# power.net
KiCad netlist of a schematic drawn in Altium Designer
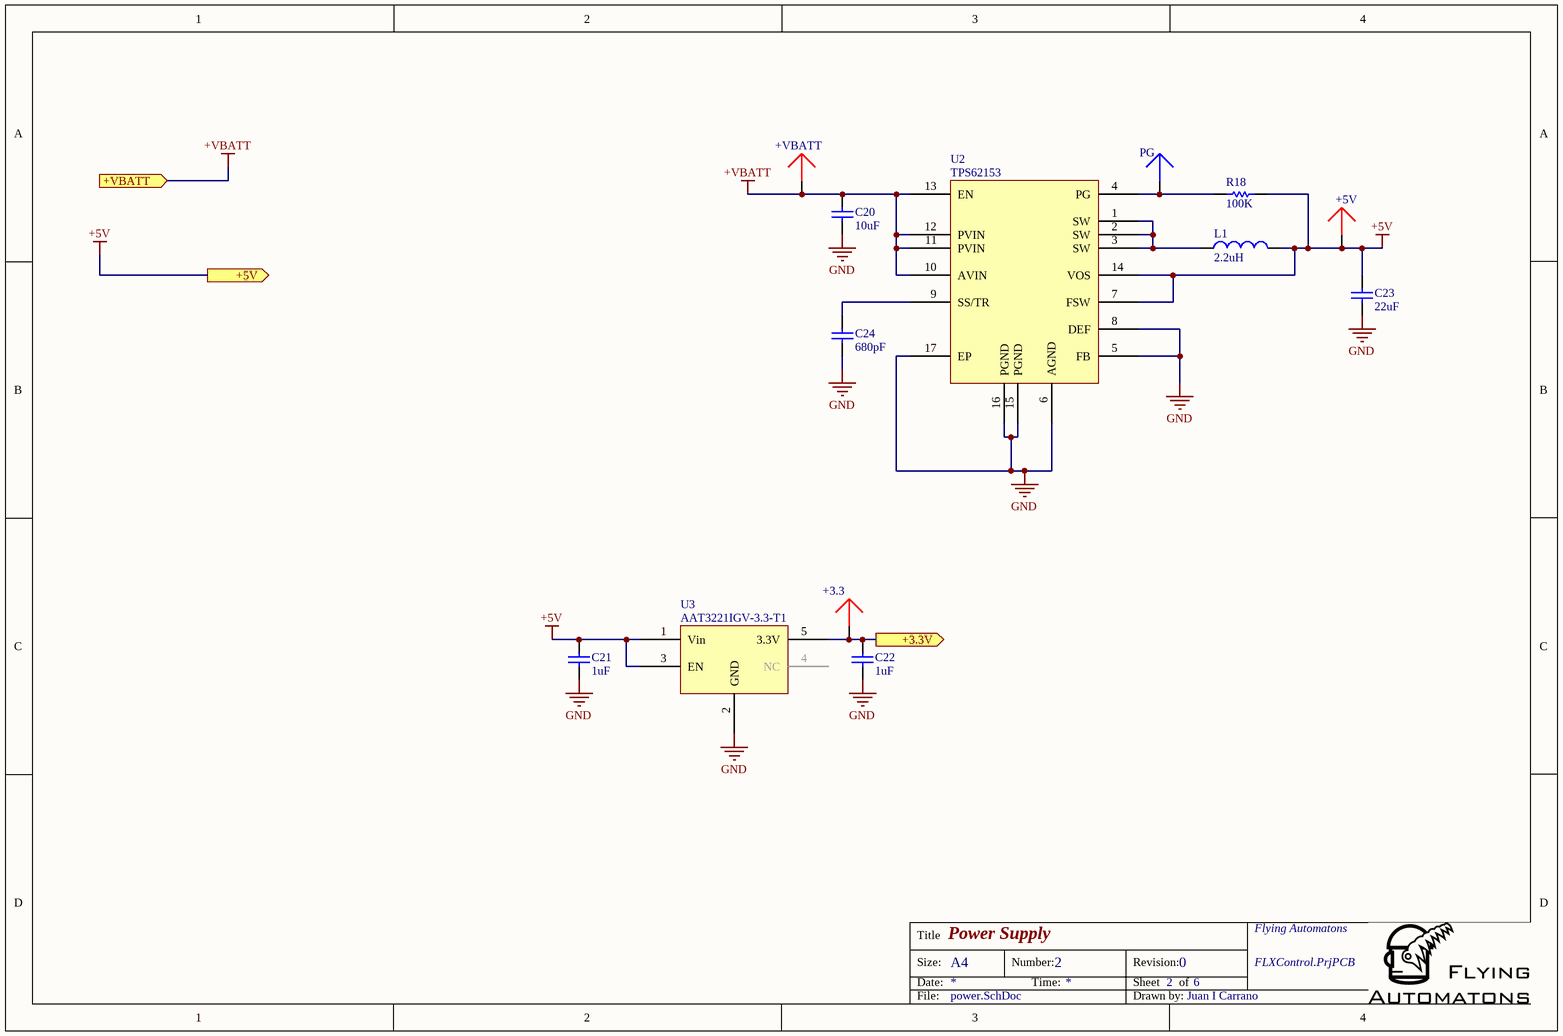
[diagram p0: power.SchDoc]

(export (version "E")
  (design (tool "Eeschema 10.0.6"))
  (components
    (comp (ref "+3.3")
      (value "TESTPOINT-ARROW-RED")
      (footprint "G-PIN_1mm-CIRCLE")
      (description "Tespoint for Power Trace")
      (libsource (lib "Connector#csv") (part "TESTP_PWR_1mm"))
    )
    (comp (ref "+5V")
      (value "TESTPOINT-ARROW-RED")
      (footprint "G-PIN_1mm-CIRCLE")
      (description "Tespoint for Power Trace")
      (libsource (lib "Connector#csv") (part "TESTP_PWR_1mm"))
    )
    (comp (ref "+VBATT")
      (value "TESTPOINT-ARROW-RED")
      (footprint "G-PIN_1mm-CIRCLE")
      (description "Tespoint for Power Trace")
      (libsource (lib "Connector#csv") (part "TESTP_PWR_1mm"))
    )
    (comp (ref "C20")
      (value "10uF")
      (footprint "CAPC3216L")
      (description "CAP CER 10UF 25V Y5V 1206")
      (fields (field (name "MANUFACTURER PART NUMBER") "TMK316F106ZL-T"))
      (libsource (lib "Passive#csv") (part "CAP_10u_1206_25V_Y5V"))
    )
    (comp (ref "C21")
      (value "1uF")
      (footprint "CAPC1608L")
      (description "CAP CER 1UF 25V 10% X5R 0603")
      (fields (field (name "MANUFACTURER PART NUMBER") "TMK107BJ105KA-T"))
      (libsource (lib "Passive#csv") (part "CAP_1u_0603_25V_X5R_10%"))
    )
    (comp (ref "C22")
      (value "1uF")
      (footprint "CAPC1608L")
      (description "CAP CER 1UF 25V 10% X5R 0603")
      (fields (field (name "MANUFACTURER PART NUMBER") "TMK107BJ105KA-T"))
      (libsource (lib "Passive#csv") (part "CAP_1u_0603_25V_X5R_10%"))
    )
    (comp (ref "C23")
      (value "22uF")
      (footprint "CAPC3216L")
      (description "CAP CER 22UF 16V 10% X5R 1206")
      (fields
        (field (name "MANUFACTURER") "Samsung Electro-Mechanics America, Inc")
        (field (name "MANUFACTURER PART NUMBER") "CL31A226KOCLFNC")
      )
      (libsource (lib "Passive#csv") (part "CAP_22u_1206_16V_X5R_10%"))
    )
    (comp (ref "C24")
      (value "680pF")
      (footprint "CAPC1608L")
      (description "CAP CER 680PF 50V 5% NP0 0603")
      (fields
        (field (name "MANUFACTURER") "Samsung Electro-Mechanics America, Inc")
        (field (name "MANUFACTURER PART NUMBER") "CL10C681JB8NFNC")
      )
      (libsource (lib "Passive#csv") (part "CAP_680p_0603_50V_NP0_5%"))
    )
    (comp (ref "L1")
      (value "2.2uH")
      (footprint "X-TDK_FLF3215")
      (description "INDUCTOR 2.2UH 1.4A 20% SMD")
      (fields
        (field (name "MANUFACTURER") "TDK Corporation")
        (field (name "MANUFACTURER PART NUMBER") "FLF3215T-2R2M")
      )
      (libsource (lib "Passive#csv") (part "IND_2u2_SMD_1A4_20%_3.2x2.5"))
    )
    (comp (ref "PG")
      (value "TESTPOINT-ARROW-BLUE")
      (footprint "G-PIN_1mm-CIRCLE")
      (description "Tespoint")
      (libsource (lib "Connector#csv") (part "TESTP_SIG_1mm"))
    )
    (comp (ref "R18")
      (value "100K")
      (footprint "RESC1608L")
      (description "RES 100K OHM 1/10W 1% 0603 SMD")
      (fields
        (field (name "MANUFACTURER") "Rohm Semiconductor")
        (field (name "MANUFACTURER PART NUMBER") "MCR03ERTF1003")
      )
      (libsource (lib "Passive#csv") (part "RES_100K_0603_0W1_1%"))
    )
    (comp (ref "U2")
      (value "TPS6215x")
      (footprint "JEDEC_MO-220VEED-4")
      (description "3-17V 1A Step-Down Converter in 3x3 QFN Package")
      (fields
        (field (name "MANUFACTURER PART NUMBER") "TPS62153")
        (field (name "MANUFACTURER") "Texas Instruments")
        (field (name "DRAWN BY") "Juan I Carrano")
      )
      (libsource (lib "Power_IC#csv") (part "x-TI_TPS62153"))
    )
    (comp (ref "U3")
      (value "LREG_3T_5pinA_EN_3.3V")
      (footprint "JEDEC_MO-178AA")
      (description "150 mA LDO Linear Regulator, SOT23-5")
      (fields
        (field (name "MANUFACTURER") "Skyworks Solutions Inc")
        (field (name "MANUFACTURER PART NUMBER") "AAT3221IGV-3.3-T1")
      )
      (libsource (lib "Power_IC#csv") (part "g-LREG_3V3_0A15_EN_SOT753"))
    )
  )
  (nets
    (net (code "1") (name "+5V") (class "Default")
      (node (ref "+5V") (pin "1") (pinfunction "1_1") (pintype "passive"))
      (node (ref "C21") (pin "1") (pinfunction "1_1") (pintype "passive"))
      (node (ref "C23") (pin "1") (pinfunction "1_1") (pintype "passive"))
      (node (ref "L1") (pin "2") (pinfunction "2_2") (pintype "passive"))
      (node (ref "R18") (pin "1") (pinfunction "1_1") (pintype "passive"))
      (node (ref "U2") (pin "14") (pinfunction "VOS_14") (pintype "passive"))
      (node (ref "U2") (pin "7") (pinfunction "FSW_7") (pintype "passive"))
      (node (ref "U3") (pin "1") (pinfunction "Vin_1") (pintype "power_in"))
      (node (ref "U3") (pin "3") (pinfunction "EN_3") (pintype "passive"))
    )
    (net (code "2") (name "+VBATT") (class "Default")
      (node (ref "+VBATT") (pin "1") (pinfunction "1_1") (pintype "passive"))
      (node (ref "C20") (pin "1") (pinfunction "1_1") (pintype "passive"))
      (node (ref "U2") (pin "10") (pinfunction "AVIN_10") (pintype "passive"))
      (node (ref "U2") (pin "11") (pinfunction "PVIN_11") (pintype "passive"))
      (node (ref "U2") (pin "12") (pinfunction "PVIN_12") (pintype "passive"))
      (node (ref "U2") (pin "13") (pinfunction "EN_13") (pintype "passive"))
    )
    (net (code "3") (name "/+3.3V") (class "Default")
      (node (ref "+3.3") (pin "1") (pinfunction "1_1") (pintype "passive"))
      (node (ref "C22") (pin "1") (pinfunction "1_1") (pintype "passive"))
      (node (ref "U3") (pin "5") (pinfunction "3.3V_5") (pintype "power_in"))
    )
    (net (code "4") (name "GND") (class "Default")
      (node (ref "C20") (pin "2") (pinfunction "2_2") (pintype "passive"))
      (node (ref "C21") (pin "2") (pinfunction "2_2") (pintype "passive"))
      (node (ref "C22") (pin "2") (pinfunction "2_2") (pintype "passive"))
      (node (ref "C23") (pin "2") (pinfunction "2_2") (pintype "passive"))
      (node (ref "C24") (pin "2") (pinfunction "2_2") (pintype "passive"))
      (node (ref "U2") (pin "15") (pinfunction "PGND_15") (pintype "passive"))
      (node (ref "U2") (pin "16") (pinfunction "PGND_16") (pintype "passive"))
      (node (ref "U2") (pin "17") (pinfunction "EP_17") (pintype "passive"))
      (node (ref "U2") (pin "5") (pinfunction "FB_5") (pintype "passive"))
      (node (ref "U2") (pin "6") (pinfunction "AGND_6") (pintype "passive"))
      (node (ref "U2") (pin "8") (pinfunction "DEF_8") (pintype "passive"))
      (node (ref "U3") (pin "2") (pinfunction "GND_2") (pintype "passive"))
    )
    (net (code "5") (name "Net-(L1-Pad1)") (class "Default")
      (node (ref "L1") (pin "1") (pinfunction "1_1") (pintype "passive"))
      (node (ref "U2") (pin "1") (pinfunction "SW_1") (pintype "passive"))
      (node (ref "U2") (pin "2") (pinfunction "SW_2") (pintype "passive"))
      (node (ref "U2") (pin "3") (pinfunction "SW_3") (pintype "passive"))
    )
    (net (code "6") (name "Net-(U2-PG)") (class "Default")
      (node (ref "PG") (pin "1") (pinfunction "1_1") (pintype "passive"))
      (node (ref "R18") (pin "2") (pinfunction "2_2") (pintype "passive"))
      (node (ref "U2") (pin "4") (pinfunction "PG_4") (pintype "passive"))
    )
    (net (code "7") (name "Net-(U2-SS{slash}TR)") (class "Default")
      (node (ref "C24") (pin "1") (pinfunction "1_1") (pintype "passive"))
      (node (ref "U2") (pin "9") (pinfunction "SS/TR_9") (pintype "passive"))
    )
    (net (code "8") (name "unconnected-(U3-NC-Pad4)") (class "Default")
      (node (ref "U3") (pin "4") (pinfunction "NC_4") (pintype "passive"))
    )
  )
)
